# bucket.net
KiCad netlist of a schematic drawn in EAGLE
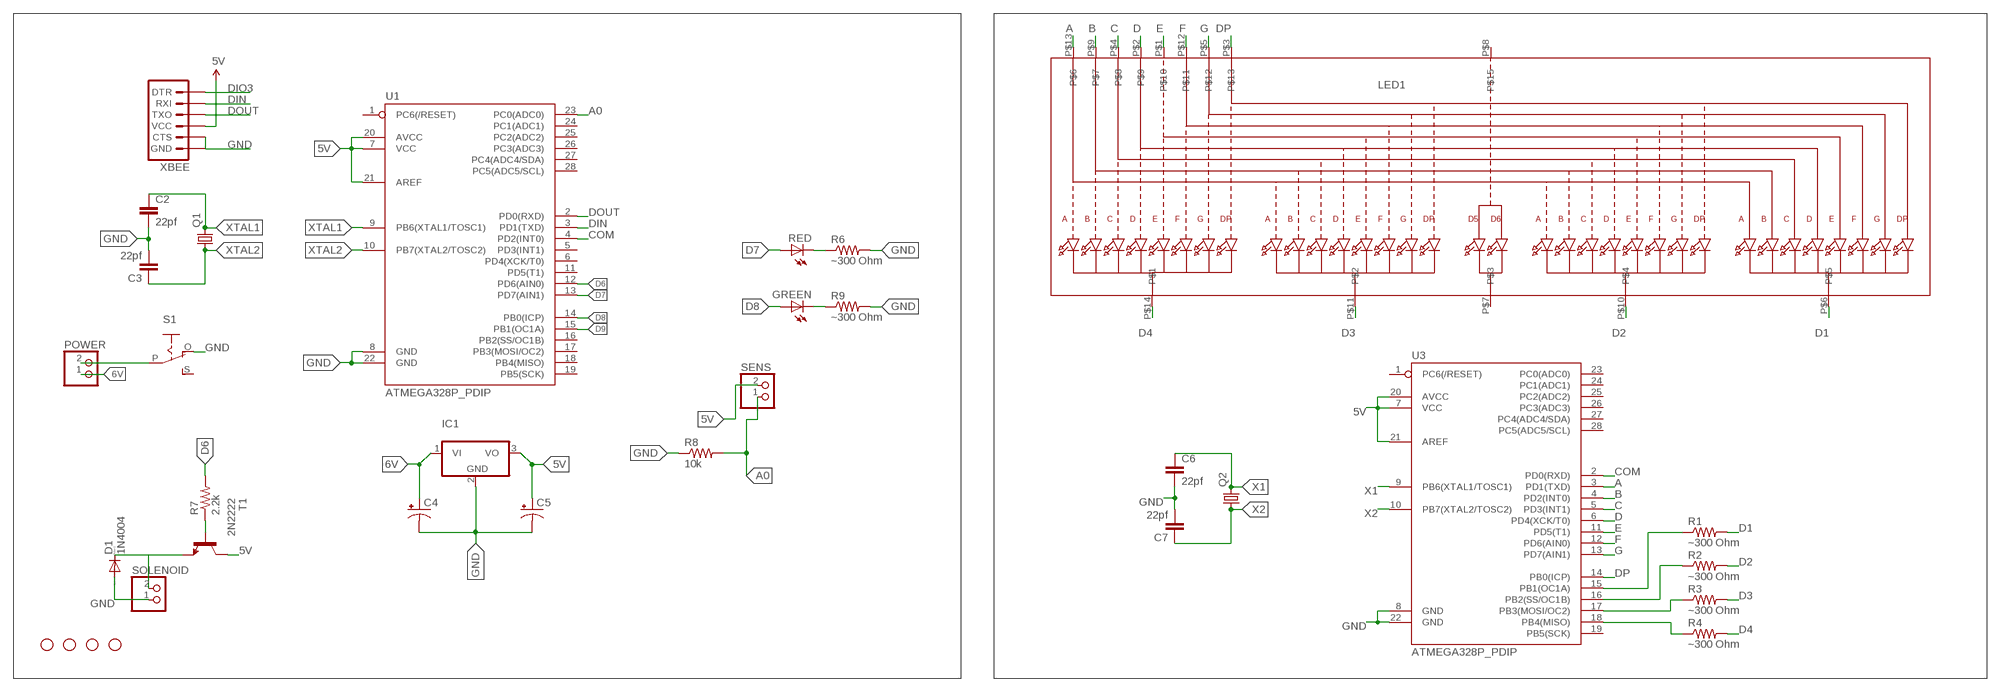
[diagram p0: schematic, sheet 1]

(export (version "E")
  (design (tool "Eeschema 10.0.6"))
  (components
    (comp (ref "C2")
      (value "22pf")
      (footprint "eagle-import:1206")
      (libsource (lib "eagle-import") (part "CAP1206"))
    )
    (comp (ref "C3")
      (value "22pf")
      (footprint "eagle-import:1206")
      (libsource (lib "eagle-import") (part "CAP1206"))
    )
    (comp (ref "C4")
      (value "CAP_POL1206")
      (footprint "eagle-import:EIA3216")
      (libsource (lib "eagle-import") (part "CAP_POL1206"))
    )
    (comp (ref "C5")
      (value "CAP_POL1206")
      (footprint "eagle-import:EIA3216")
      (libsource (lib "eagle-import") (part "CAP_POL1206"))
    )
    (comp (ref "C6")
      (value "22pf")
      (footprint "eagle-import:1206")
      (libsource (lib "eagle-import") (part "CAP1206"))
    )
    (comp (ref "C7")
      (value "22pf")
      (footprint "eagle-import:1206")
      (libsource (lib "eagle-import") (part "CAP1206"))
    )
    (comp (ref "D1")
      (value "1N4004")
      (footprint "eagle-import:DO41-10")
      (libsource (lib "eagle-import") (part "1N4004"))
    )
    (comp (ref "GREEN")
      (value "HSMC-C265")
      (footprint "eagle-import:HSMC-C265")
      (libsource (lib "eagle-import") (part "HSMC-C265"))
    )
    (comp (ref "IC1")
      (value "7805T")
      (footprint "eagle-import:TO220H")
      (libsource (lib "eagle-import") (part "78T05"))
    )
    (comp (ref "LED1")
      (value "DISP_SEGMENT_4DIGIT_BL-Q56C43")
      (footprint "eagle-import:SEGMENT-BL-Q56C43")
      (libsource (lib "eagle-import") (part "DISP_SEGMENT_4DIGIT_BL-Q56C43"))
    )
    (comp (ref "POWER")
      (value "JST_2PIN-THM-RA")
      (footprint "eagle-import:JST-PH-2-THM-RA")
      (libsource (lib "eagle-import") (part "JST_2PIN-THM-RA"))
    )
    (comp (ref "Q1")
      (value "CRYSTALHC49S")
      (footprint "eagle-import:HC49_S")
      (libsource (lib "eagle-import") (part "CRYSTALHC49S"))
    )
    (comp (ref "Q2")
      (value "CRYSTALHC49S")
      (footprint "eagle-import:HC49_S")
      (libsource (lib "eagle-import") (part "CRYSTALHC49S"))
    )
    (comp (ref "R1")
      (value "~300 Ohm")
      (footprint "eagle-import:1206")
      (libsource (lib "eagle-import") (part "RESISTOR1206"))
    )
    (comp (ref "R2")
      (value "~300 Ohm")
      (footprint "eagle-import:1206")
      (libsource (lib "eagle-import") (part "RESISTOR1206"))
    )
    (comp (ref "R3")
      (value "~300 Ohm")
      (footprint "eagle-import:1206")
      (libsource (lib "eagle-import") (part "RESISTOR1206"))
    )
    (comp (ref "R4")
      (value "~300 Ohm")
      (footprint "eagle-import:1206")
      (libsource (lib "eagle-import") (part "RESISTOR1206"))
    )
    (comp (ref "R6")
      (value "~300 Ohm")
      (footprint "eagle-import:1206")
      (libsource (lib "eagle-import") (part "RESISTOR1206"))
    )
    (comp (ref "R7")
      (value "2.2k")
      (footprint "eagle-import:1206")
      (libsource (lib "eagle-import") (part "RESISTOR1206"))
    )
    (comp (ref "R8")
      (value "10k")
      (footprint "eagle-import:1206")
      (libsource (lib "eagle-import") (part "RESISTOR1206"))
    )
    (comp (ref "R9")
      (value "~300 Ohm")
      (footprint "eagle-import:1206")
      (libsource (lib "eagle-import") (part "RESISTOR1206"))
    )
    (comp (ref "RED")
      (value "HSMC-C265")
      (footprint "eagle-import:HSMC-C265")
      (libsource (lib "eagle-import") (part "HSMC-C265"))
    )
    (comp (ref "S1")
      (value "EG1218S")
      (footprint "eagle-import:EG1218")
      (libsource (lib "eagle-import") (part "EG1218S"))
    )
    (comp (ref "SENS")
      (value "JST_2PIN-THM-RA")
      (footprint "eagle-import:JST-PH-2-THM-RA")
      (libsource (lib "eagle-import") (part "JST_2PIN-THM-RA"))
    )
    (comp (ref "SOLENOID")
      (value "JST_2PIN-THM-RA")
      (footprint "eagle-import:JST-PH-2-THM-RA")
      (libsource (lib "eagle-import") (part "JST_2PIN-THM-RA"))
    )
    (comp (ref "STANDOFF1")
      (value "STAND-OFF")
      (footprint "eagle-import:STAND-OFF")
      (libsource (lib "eagle-import") (part "STAND-OFF"))
    )
    (comp (ref "STANDOFF2")
      (value "STAND-OFF")
      (footprint "eagle-import:STAND-OFF")
      (libsource (lib "eagle-import") (part "STAND-OFF"))
    )
    (comp (ref "STANDOFF3")
      (value "STAND-OFF")
      (footprint "eagle-import:STAND-OFF")
      (libsource (lib "eagle-import") (part "STAND-OFF"))
    )
    (comp (ref "STANDOFF4")
      (value "STAND-OFF")
      (footprint "eagle-import:STAND-OFF")
      (libsource (lib "eagle-import") (part "STAND-OFF"))
    )
    (comp (ref "T1")
      (value "2N2222")
      (footprint "eagle-import:TO92-EBC-OVAL")
      (libsource (lib "eagle-import") (part "2N2222"))
    )
    (comp (ref "U1")
      (value "ATMEGA328P_PDIP")
      (footprint "eagle-import:DIL28-3")
      (libsource (lib "eagle-import") (part "ATMEGA328P_PDIP"))
    )
    (comp (ref "U3")
      (value "ATMEGA328P_PDIP")
      (footprint "eagle-import:DIL28-3")
      (libsource (lib "eagle-import") (part "ATMEGA328P_PDIP"))
    )
    (comp (ref "XBEE")
      (value "ARDUINO_SERIAL_PROGRAMPTH")
      (footprint "eagle-import:1X06")
      (libsource (lib "eagle-import") (part "ARDUINO_SERIAL_PROGRAMPTH"))
    )
  )
  (nets
    (net (code "1") (name "/A") (class "Default")
      (node (ref "LED1") (pin "P$13") (pinfunction "P$6_P$13") (pintype "bidirectional"))
      (node (ref "U3") (pin "3") (pinfunction "PD1(TXD)_3") (pintype "bidirectional"))
    )
    (net (code "2") (name "/B") (class "Default")
      (node (ref "LED1") (pin "P$9") (pinfunction "P$7_P$9") (pintype "bidirectional"))
      (node (ref "U3") (pin "4") (pinfunction "PD2(INT0)_4") (pintype "bidirectional"))
    )
    (net (code "3") (name "/C") (class "Default")
      (node (ref "LED1") (pin "P$4") (pinfunction "P$8_P$4") (pintype "bidirectional"))
      (node (ref "U3") (pin "5") (pinfunction "PD3(INT1)_5") (pintype "bidirectional"))
    )
    (net (code "4") (name "/COM") (class "Default")
      (node (ref "U1") (pin "4") (pinfunction "PD2(INT0)_4") (pintype "bidirectional"))
      (node (ref "U3") (pin "2") (pinfunction "PD0(RXD)_2") (pintype "bidirectional"))
    )
    (net (code "5") (name "/D") (class "Default")
      (node (ref "LED1") (pin "P$2") (pinfunction "P$9_P$2") (pintype "bidirectional"))
      (node (ref "U3") (pin "6") (pinfunction "PD4(XCK/T0)_6") (pintype "bidirectional"))
    )
    (net (code "6") (name "/D1") (class "Default")
      (node (ref "LED1") (pin "P$6") (pinfunction "P$5_P$6") (pintype "bidirectional"))
      (node (ref "R1") (pin "2") (pinfunction "2_2") (pintype "passive"))
    )
    (net (code "7") (name "/D2") (class "Default")
      (node (ref "LED1") (pin "P$10") (pinfunction "P$4_P$10") (pintype "bidirectional"))
      (node (ref "R2") (pin "2") (pinfunction "2_2") (pintype "passive"))
    )
    (net (code "8") (name "/D3") (class "Default")
      (node (ref "LED1") (pin "P$11") (pinfunction "P$2_P$11") (pintype "bidirectional"))
      (node (ref "R3") (pin "2") (pinfunction "2_2") (pintype "passive"))
    )
    (net (code "9") (name "/D4") (class "Default")
      (node (ref "LED1") (pin "P$14") (pinfunction "P$1_P$14") (pintype "bidirectional"))
      (node (ref "R4") (pin "2") (pinfunction "2_2") (pintype "passive"))
    )
    (net (code "10") (name "/DIN") (class "Default")
      (node (ref "U1") (pin "3") (pinfunction "PD1(TXD)_3") (pintype "bidirectional"))
      (node (ref "XBEE") (pin "2") (pinfunction "RXI_2") (pintype "passive"))
    )
    (net (code "11") (name "/DIO3") (class "Default")
      (node (ref "XBEE") (pin "1") (pinfunction "DTR_1") (pintype "passive"))
    )
    (net (code "12") (name "/DOUT") (class "Default")
      (node (ref "U1") (pin "2") (pinfunction "PD0(RXD)_2") (pintype "bidirectional"))
      (node (ref "XBEE") (pin "3") (pinfunction "TXO_3") (pintype "passive"))
    )
    (net (code "13") (name "/DP") (class "Default")
      (node (ref "LED1") (pin "P$3") (pinfunction "P$13_P$3") (pintype "bidirectional"))
      (node (ref "U3") (pin "14") (pinfunction "PB0(ICP)_14") (pintype "bidirectional"))
    )
    (net (code "14") (name "/E") (class "Default")
      (node (ref "LED1") (pin "P$1") (pinfunction "P$10_P$1") (pintype "bidirectional"))
      (node (ref "U3") (pin "11") (pinfunction "PD5(T1)_11") (pintype "bidirectional"))
    )
    (net (code "15") (name "/F") (class "Default")
      (node (ref "LED1") (pin "P$12") (pinfunction "P$11_P$12") (pintype "bidirectional"))
      (node (ref "U3") (pin "12") (pinfunction "PD6(AIN0)_12") (pintype "bidirectional"))
    )
    (net (code "16") (name "/G") (class "Default")
      (node (ref "LED1") (pin "P$5") (pinfunction "P$12_P$5") (pintype "bidirectional"))
      (node (ref "U3") (pin "13") (pinfunction "PD7(AIN1)_13") (pintype "bidirectional"))
    )
    (net (code "17") (name "5V") (class "Default")
      (node (ref "C5") (pin "A") (pinfunction "+_A") (pintype "passive"))
      (node (ref "IC1") (pin "3") (pinfunction "VO_3") (pintype "passive"))
      (node (ref "SENS") (pin "2") (pinfunction "1_2") (pintype "passive"))
      (node (ref "T1") (pin "E") (pinfunction "C_E") (pintype "passive"))
      (node (ref "U1") (pin "20") (pinfunction "AVCC_20") (pintype "bidirectional"))
      (node (ref "U1") (pin "21") (pinfunction "AREF_21") (pintype "bidirectional"))
      (node (ref "U1") (pin "7") (pinfunction "VCC_7") (pintype "bidirectional"))
      (node (ref "U3") (pin "20") (pinfunction "AVCC_20") (pintype "bidirectional"))
      (node (ref "U3") (pin "21") (pinfunction "AREF_21") (pintype "bidirectional"))
      (node (ref "U3") (pin "7") (pinfunction "VCC_7") (pintype "bidirectional"))
      (node (ref "XBEE") (pin "4") (pinfunction "VCC_4") (pintype "passive"))
    )
    (net (code "18") (name "6V") (class "Default")
      (node (ref "C4") (pin "A") (pinfunction "+_A") (pintype "passive"))
      (node (ref "IC1") (pin "1") (pinfunction "VI_1") (pintype "input"))
      (node (ref "POWER") (pin "1") (pinfunction "2_1") (pintype "passive"))
    )
    (net (code "19") (name "A0") (class "Default")
      (node (ref "R8") (pin "2") (pinfunction "2_2") (pintype "passive"))
      (node (ref "SENS") (pin "1") (pinfunction "2_1") (pintype "passive"))
      (node (ref "U1") (pin "23") (pinfunction "PC0(ADC0)_23") (pintype "bidirectional"))
    )
    (net (code "20") (name "D6") (class "Default")
      (node (ref "R7") (pin "2") (pinfunction "2_2") (pintype "passive"))
      (node (ref "U1") (pin "12") (pinfunction "PD6(AIN0)_12") (pintype "bidirectional"))
    )
    (net (code "21") (name "D7") (class "Default")
      (node (ref "RED") (pin "A") (pinfunction "A_A") (pintype "passive"))
      (node (ref "U1") (pin "13") (pinfunction "PD7(AIN1)_13") (pintype "bidirectional"))
    )
    (net (code "22") (name "D8") (class "Default")
      (node (ref "GREEN") (pin "A") (pinfunction "A_A") (pintype "passive"))
      (node (ref "U1") (pin "14") (pinfunction "PB0(ICP)_14") (pintype "bidirectional"))
    )
    (net (code "23") (name "D9") (class "Default")
      (node (ref "U1") (pin "15") (pinfunction "PB1(OC1A)_15") (pintype "bidirectional"))
    )
    (net (code "24") (name "GND") (class "Default")
      (node (ref "C2") (pin "2") (pinfunction "2_2") (pintype "passive"))
      (node (ref "C3") (pin "2") (pinfunction "2_2") (pintype "passive"))
      (node (ref "C4") (pin "C") (pinfunction "-_C") (pintype "passive"))
      (node (ref "C5") (pin "C") (pinfunction "-_C") (pintype "passive"))
      (node (ref "C6") (pin "2") (pinfunction "2_2") (pintype "passive"))
      (node (ref "C7") (pin "2") (pinfunction "2_2") (pintype "passive"))
      (node (ref "D1") (pin "A") (pinfunction "A_A") (pintype "passive"))
      (node (ref "IC1") (pin "2") (pinfunction "GND_2") (pintype "passive"))
      (node (ref "R6") (pin "2") (pinfunction "2_2") (pintype "passive"))
      (node (ref "R8") (pin "1") (pinfunction "1_1") (pintype "passive"))
      (node (ref "R9") (pin "2") (pinfunction "2_2") (pintype "passive"))
      (node (ref "S1") (pin "O") (pinfunction "O_O") (pintype "passive"))
      (node (ref "SOLENOID") (pin "1") (pinfunction "2_1") (pintype "passive"))
      (node (ref "U1") (pin "22") (pinfunction "GND_22") (pintype "bidirectional"))
      (node (ref "U1") (pin "8") (pinfunction "GND_8") (pintype "bidirectional"))
      (node (ref "U3") (pin "22") (pinfunction "GND_22") (pintype "bidirectional"))
      (node (ref "U3") (pin "8") (pinfunction "GND_8") (pintype "bidirectional"))
      (node (ref "XBEE") (pin "5") (pinfunction "CTS_5") (pintype "passive"))
      (node (ref "XBEE") (pin "6") (pinfunction "GND_6") (pintype "passive"))
    )
    (net (code "25") (name "Net-(GREEN-PadC)") (class "Default")
      (node (ref "GREEN") (pin "C") (pinfunction "C_C") (pintype "passive"))
      (node (ref "R9") (pin "1") (pinfunction "1_1") (pintype "passive"))
    )
    (net (code "26") (name "Net-(POWER-1)") (class "Default")
      (node (ref "POWER") (pin "2") (pinfunction "1_2") (pintype "passive"))
      (node (ref "S1") (pin "P") (pinfunction "P_P") (pintype "passive"))
    )
    (net (code "27") (name "Net-(R6-Pad1)") (class "Default")
      (node (ref "R6") (pin "1") (pinfunction "1_1") (pintype "passive"))
      (node (ref "RED") (pin "C") (pinfunction "C_C") (pintype "passive"))
    )
    (net (code "28") (name "Net-(R7-Pad1)") (class "Default")
      (node (ref "R7") (pin "1") (pinfunction "1_1") (pintype "passive"))
      (node (ref "T1") (pin "B") (pinfunction "B_B") (pintype "passive"))
    )
    (net (code "29") (name "Net-(SOLENOID-1)") (class "Default")
      (node (ref "D1") (pin "C") (pinfunction "C_C") (pintype "passive"))
      (node (ref "SOLENOID") (pin "2") (pinfunction "1_2") (pintype "passive"))
      (node (ref "T1") (pin "C") (pinfunction "E_C") (pintype "passive"))
    )
    (net (code "30") (name "Net-(U3-PB1(OC1A))") (class "Default")
      (node (ref "R1") (pin "1") (pinfunction "1_1") (pintype "passive"))
      (node (ref "U3") (pin "15") (pinfunction "PB1(OC1A)_15") (pintype "bidirectional"))
    )
    (net (code "31") (name "Net-(U3-PB2(SS{slash}OC1B))") (class "Default")
      (node (ref "R2") (pin "1") (pinfunction "1_1") (pintype "passive"))
      (node (ref "U3") (pin "16") (pinfunction "PB2(SS/OC1B)_16") (pintype "bidirectional"))
    )
    (net (code "32") (name "Net-(U3-PB3(MOSI{slash}OC2))") (class "Default")
      (node (ref "R3") (pin "1") (pinfunction "1_1") (pintype "passive"))
      (node (ref "U3") (pin "17") (pinfunction "PB3(MOSI/OC2)_17") (pintype "bidirectional"))
    )
    (net (code "33") (name "Net-(U3-PB4(MISO))") (class "Default")
      (node (ref "R4") (pin "1") (pinfunction "1_1") (pintype "passive"))
      (node (ref "U3") (pin "18") (pinfunction "PB4(MISO)_18") (pintype "bidirectional"))
    )
    (net (code "34") (name "X1") (class "Default")
      (node (ref "C6") (pin "1") (pinfunction "1_1") (pintype "passive"))
      (node (ref "Q2") (pin "2") (pinfunction "2_2") (pintype "passive"))
      (node (ref "U3") (pin "9") (pinfunction "PB6(XTAL1/TOSC1)_9") (pintype "bidirectional"))
    )
    (net (code "35") (name "X2") (class "Default")
      (node (ref "C7") (pin "1") (pinfunction "1_1") (pintype "passive"))
      (node (ref "Q2") (pin "1") (pinfunction "1_1") (pintype "passive"))
      (node (ref "U3") (pin "10") (pinfunction "PB7(XTAL2/TOSC2)_10") (pintype "bidirectional"))
    )
    (net (code "36") (name "XTAL1") (class "Default")
      (node (ref "C2") (pin "1") (pinfunction "1_1") (pintype "passive"))
      (node (ref "Q1") (pin "2") (pinfunction "2_2") (pintype "passive"))
      (node (ref "U1") (pin "9") (pinfunction "PB6(XTAL1/TOSC1)_9") (pintype "bidirectional"))
    )
    (net (code "37") (name "XTAL2") (class "Default")
      (node (ref "C3") (pin "1") (pinfunction "1_1") (pintype "passive"))
      (node (ref "Q1") (pin "1") (pinfunction "1_1") (pintype "passive"))
      (node (ref "U1") (pin "10") (pinfunction "PB7(XTAL2/TOSC2)_10") (pintype "bidirectional"))
    )
    (net (code "38") (name "unconnected-(LED1-P$3-PadP$7)") (class "Default")
      (node (ref "LED1") (pin "P$7") (pinfunction "P$3_P$7") (pintype "bidirectional"))
    )
    (net (code "39") (name "unconnected-(LED1-P$15-PadP$8)") (class "Default")
      (node (ref "LED1") (pin "P$8") (pinfunction "P$15_P$8") (pintype "bidirectional"))
    )
    (net (code "40") (name "unconnected-(S1-PadS)") (class "Default")
      (node (ref "S1") (pin "S") (pinfunction "S_S") (pintype "passive"))
    )
    (net (code "41") (name "unconnected-(U1-PB2(SS{slash}OC1B)-Pad16)") (class "Default")
      (node (ref "U1") (pin "16") (pinfunction "PB2(SS/OC1B)_16") (pintype "bidirectional"))
    )
    (net (code "42") (name "unconnected-(U1-PB3(MOSI{slash}OC2)-Pad17)") (class "Default")
      (node (ref "U1") (pin "17") (pinfunction "PB3(MOSI/OC2)_17") (pintype "bidirectional"))
    )
    (net (code "43") (name "unconnected-(U1-PB4(MISO)-Pad18)") (class "Default")
      (node (ref "U1") (pin "18") (pinfunction "PB4(MISO)_18") (pintype "bidirectional"))
    )
    (net (code "44") (name "unconnected-(U1-PB5(SCK)-Pad19)") (class "Default")
      (node (ref "U1") (pin "19") (pinfunction "PB5(SCK)_19") (pintype "bidirectional"))
    )
    (net (code "45") (name "unconnected-(U1-PC1(ADC1)-Pad24)") (class "Default")
      (node (ref "U1") (pin "24") (pinfunction "PC1(ADC1)_24") (pintype "bidirectional"))
    )
    (net (code "46") (name "unconnected-(U1-PC2(ADC2)-Pad25)") (class "Default")
      (node (ref "U1") (pin "25") (pinfunction "PC2(ADC2)_25") (pintype "bidirectional"))
    )
    (net (code "47") (name "unconnected-(U1-PC3(ADC3)-Pad26)") (class "Default")
      (node (ref "U1") (pin "26") (pinfunction "PC3(ADC3)_26") (pintype "bidirectional"))
    )
    (net (code "48") (name "unconnected-(U1-PC4(ADC4{slash}SDA)-Pad27)") (class "Default")
      (node (ref "U1") (pin "27") (pinfunction "PC4(ADC4/SDA)_27") (pintype "bidirectional"))
    )
    (net (code "49") (name "unconnected-(U1-PC5(ADC5{slash}SCL)-Pad28)") (class "Default")
      (node (ref "U1") (pin "28") (pinfunction "PC5(ADC5/SCL)_28") (pintype "bidirectional"))
    )
    (net (code "50") (name "unconnected-(U1-PC6({slash}RESET)-Pad1)") (class "Default")
      (node (ref "U1") (pin "1") (pinfunction "PC6(/RESET)_1") (pintype "bidirectional"))
    )
    (net (code "51") (name "unconnected-(U1-PD3(INT1)-Pad5)") (class "Default")
      (node (ref "U1") (pin "5") (pinfunction "PD3(INT1)_5") (pintype "bidirectional"))
    )
    (net (code "52") (name "unconnected-(U1-PD4(XCK{slash}T0)-Pad6)") (class "Default")
      (node (ref "U1") (pin "6") (pinfunction "PD4(XCK/T0)_6") (pintype "bidirectional"))
    )
    (net (code "53") (name "unconnected-(U1-PD5(T1)-Pad11)") (class "Default")
      (node (ref "U1") (pin "11") (pinfunction "PD5(T1)_11") (pintype "bidirectional"))
    )
    (net (code "54") (name "unconnected-(U3-PB5(SCK)-Pad19)") (class "Default")
      (node (ref "U3") (pin "19") (pinfunction "PB5(SCK)_19") (pintype "bidirectional"))
    )
    (net (code "55") (name "unconnected-(U3-PC0(ADC0)-Pad23)") (class "Default")
      (node (ref "U3") (pin "23") (pinfunction "PC0(ADC0)_23") (pintype "bidirectional"))
    )
    (net (code "56") (name "unconnected-(U3-PC1(ADC1)-Pad24)") (class "Default")
      (node (ref "U3") (pin "24") (pinfunction "PC1(ADC1)_24") (pintype "bidirectional"))
    )
    (net (code "57") (name "unconnected-(U3-PC2(ADC2)-Pad25)") (class "Default")
      (node (ref "U3") (pin "25") (pinfunction "PC2(ADC2)_25") (pintype "bidirectional"))
    )
    (net (code "58") (name "unconnected-(U3-PC3(ADC3)-Pad26)") (class "Default")
      (node (ref "U3") (pin "26") (pinfunction "PC3(ADC3)_26") (pintype "bidirectional"))
    )
    (net (code "59") (name "unconnected-(U3-PC4(ADC4{slash}SDA)-Pad27)") (class "Default")
      (node (ref "U3") (pin "27") (pinfunction "PC4(ADC4/SDA)_27") (pintype "bidirectional"))
    )
    (net (code "60") (name "unconnected-(U3-PC5(ADC5{slash}SCL)-Pad28)") (class "Default")
      (node (ref "U3") (pin "28") (pinfunction "PC5(ADC5/SCL)_28") (pintype "bidirectional"))
    )
    (net (code "61") (name "unconnected-(U3-PC6({slash}RESET)-Pad1)") (class "Default")
      (node (ref "U3") (pin "1") (pinfunction "PC6(/RESET)_1") (pintype "bidirectional"))
    )
  )
)
